# PS_RJ45.net
KiCad netlist of a schematic drawn in Altium Designer
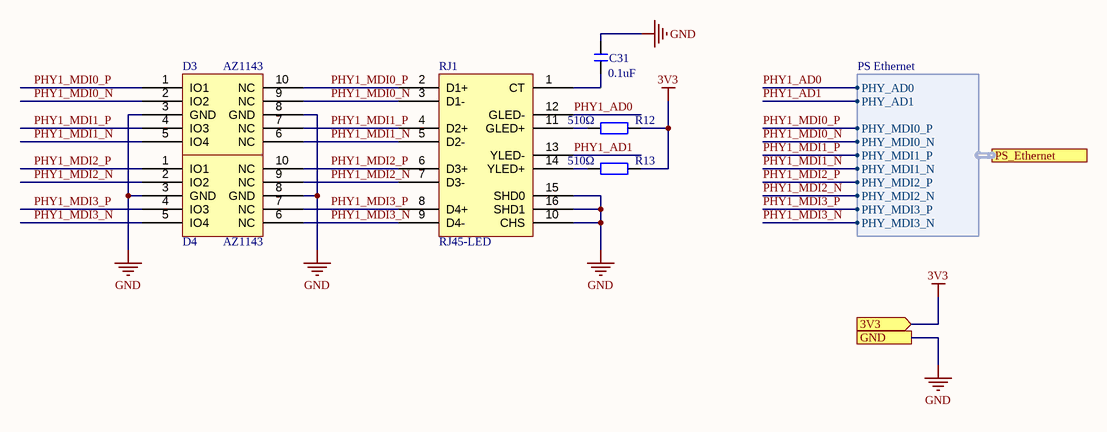
[diagram p0: PS_RJ45.SchDoc]

(export (version "E")
  (design (tool "Eeschema 10.0.6"))
  (components
    (comp (ref "C31")
      (value "0.1uF")
      (footprint "C 0603_L")
      (description "贴片电容")
      (libsource (lib "0.1 - 电阻-电容-电感") (part "C"))
    )
    (comp (ref "D3")
      (value "AZ1143")
      (footprint "DFN-10_L2.5-W1.0-P0.50-BL-A")
      (description "Transient Voltage Suppression (TVS) Diode")
      (libsource (lib "CustomizedComponents") (part "AZ1143"))
    )
    (comp (ref "D4")
      (value "AZ1143")
      (footprint "DFN-10_L2.5-W1.0-P0.50-BL-A")
      (description "Transient Voltage Suppression (TVS) Diode")
      (libsource (lib "CustomizedComponents") (part "AZ1143"))
    )
    (comp (ref "R12")
      (value "510Ω")
      (footprint "R 0603_L")
      (description "贴片电阻")
      (fields (field (name "版权归属") "来自淘宝 ID：黄晶宝石"))
      (libsource (lib "0.1 - 电阻-电容-电感") (part "R"))
    )
    (comp (ref "R13")
      (value "510Ω")
      (footprint "R 0603_L")
      (description "贴片电阻")
      (fields (field (name "版权归属") "来自淘宝 ID：黄晶宝石"))
      (libsource (lib "0.1 - 电阻-电容-电感") (part "R"))
    )
    (comp (ref "RJ1")
      (value "RJ45-LED")
      (footprint "RJ-45A16")
      (description "带灯以太网接口")
      (fields (field (name "版权归属") "封装库来自淘宝 ID：黄晶宝石"))
      (libsource (lib "0.8 - 以太网-音频-USB插座") (part "RJ45-2LED"))
    )
  )
  (nets
    (net (code "3") (name "/PHY1_AD0") (class "Default")
      (node (ref "RJ1") (pin "12") (pinfunction "GLED-_12") (pintype "passive"))
    )
    (net (code "4") (name "/PHY1_AD1") (class "Default")
      (node (ref "RJ1") (pin "13") (pinfunction "YLED-_13") (pintype "passive"))
    )
    (net (code "5") (name "/PHY1_MDI0_N") (class "Default")
      (node (ref "D3") (pin "2") (pinfunction "IO2_2") (pintype "passive"))
      (node (ref "D3") (pin "9") (pinfunction "NC_9") (pintype "passive"))
      (node (ref "RJ1") (pin "3") (pinfunction "D1-_3") (pintype "passive"))
    )
    (net (code "6") (name "/PHY1_MDI0_P") (class "Default")
      (node (ref "D3") (pin "1") (pinfunction "IO1_1") (pintype "passive"))
      (node (ref "D3") (pin "10") (pinfunction "NC_10") (pintype "passive"))
      (node (ref "RJ1") (pin "2") (pinfunction "D1+_2") (pintype "passive"))
    )
    (net (code "7") (name "/PHY1_MDI1_N") (class "Default")
      (node (ref "D3") (pin "5") (pinfunction "IO4_5") (pintype "passive"))
      (node (ref "D3") (pin "6") (pinfunction "NC_6") (pintype "passive"))
      (node (ref "RJ1") (pin "5") (pinfunction "D2-_5") (pintype "passive"))
    )
    (net (code "8") (name "/PHY1_MDI1_P") (class "Default")
      (node (ref "D3") (pin "4") (pinfunction "IO3_4") (pintype "passive"))
      (node (ref "D3") (pin "7") (pinfunction "NC_7") (pintype "passive"))
      (node (ref "RJ1") (pin "4") (pinfunction "D2+_4") (pintype "passive"))
    )
    (net (code "9") (name "/PHY1_MDI2_N") (class "Default")
      (node (ref "D4") (pin "2") (pinfunction "IO2_2") (pintype "passive"))
      (node (ref "D4") (pin "9") (pinfunction "NC_9") (pintype "passive"))
      (node (ref "RJ1") (pin "7") (pinfunction "D3-_7") (pintype "passive"))
    )
    (net (code "10") (name "/PHY1_MDI2_P") (class "Default")
      (node (ref "D4") (pin "1") (pinfunction "IO1_1") (pintype "passive"))
      (node (ref "D4") (pin "10") (pinfunction "NC_10") (pintype "passive"))
      (node (ref "RJ1") (pin "6") (pinfunction "D3+_6") (pintype "passive"))
    )
    (net (code "11") (name "/PHY1_MDI3_N") (class "Default")
      (node (ref "D4") (pin "5") (pinfunction "IO4_5") (pintype "passive"))
      (node (ref "D4") (pin "6") (pinfunction "NC_6") (pintype "passive"))
      (node (ref "RJ1") (pin "9") (pinfunction "D4-_9") (pintype "passive"))
    )
    (net (code "12") (name "/PHY1_MDI3_P") (class "Default")
      (node (ref "D4") (pin "4") (pinfunction "IO3_4") (pintype "passive"))
      (node (ref "D4") (pin "7") (pinfunction "NC_7") (pintype "passive"))
      (node (ref "RJ1") (pin "8") (pinfunction "D4+_8") (pintype "passive"))
    )
    (net (code "14") (name "3V3") (class "Default")
      (node (ref "R12") (pin "2") (pinfunction "2_2") (pintype "passive"))
      (node (ref "R13") (pin "2") (pinfunction "2_2") (pintype "passive"))
    )
    (net (code "15") (name "GND") (class "Default")
      (node (ref "C31") (pin "2") (pinfunction "2_2") (pintype "passive"))
      (node (ref "D3") (pin "3") (pinfunction "GND_3") (pintype "power_in"))
      (node (ref "D3") (pin "8") (pinfunction "GND_8") (pintype "power_in"))
      (node (ref "D4") (pin "3") (pinfunction "GND_3") (pintype "power_in"))
      (node (ref "D4") (pin "8") (pinfunction "GND_8") (pintype "power_in"))
      (node (ref "RJ1") (pin "10") (pinfunction "CHS_10") (pintype "passive"))
      (node (ref "RJ1") (pin "15") (pinfunction "SHD0_15") (pintype "passive"))
      (node (ref "RJ1") (pin "16") (pinfunction "SHD1_16") (pintype "passive"))
    )
    (net (code "16") (name "Net-(RJ1-CT)") (class "Default")
      (node (ref "C31") (pin "1") (pinfunction "1_1") (pintype "passive"))
      (node (ref "RJ1") (pin "1") (pinfunction "CT_1") (pintype "passive"))
    )
    (net (code "17") (name "Net-(RJ1-GLED+)") (class "Default")
      (node (ref "R12") (pin "1") (pinfunction "1_1") (pintype "passive"))
      (node (ref "RJ1") (pin "11") (pinfunction "GLED+_11") (pintype "passive"))
    )
    (net (code "18") (name "Net-(RJ1-YLED+)") (class "Default")
      (node (ref "R13") (pin "1") (pinfunction "1_1") (pintype "passive"))
      (node (ref "RJ1") (pin "14") (pinfunction "YLED+_14") (pintype "passive"))
    )
  )
)
